# 005.net
KiCad netlist of a schematic drawn in EAGLE
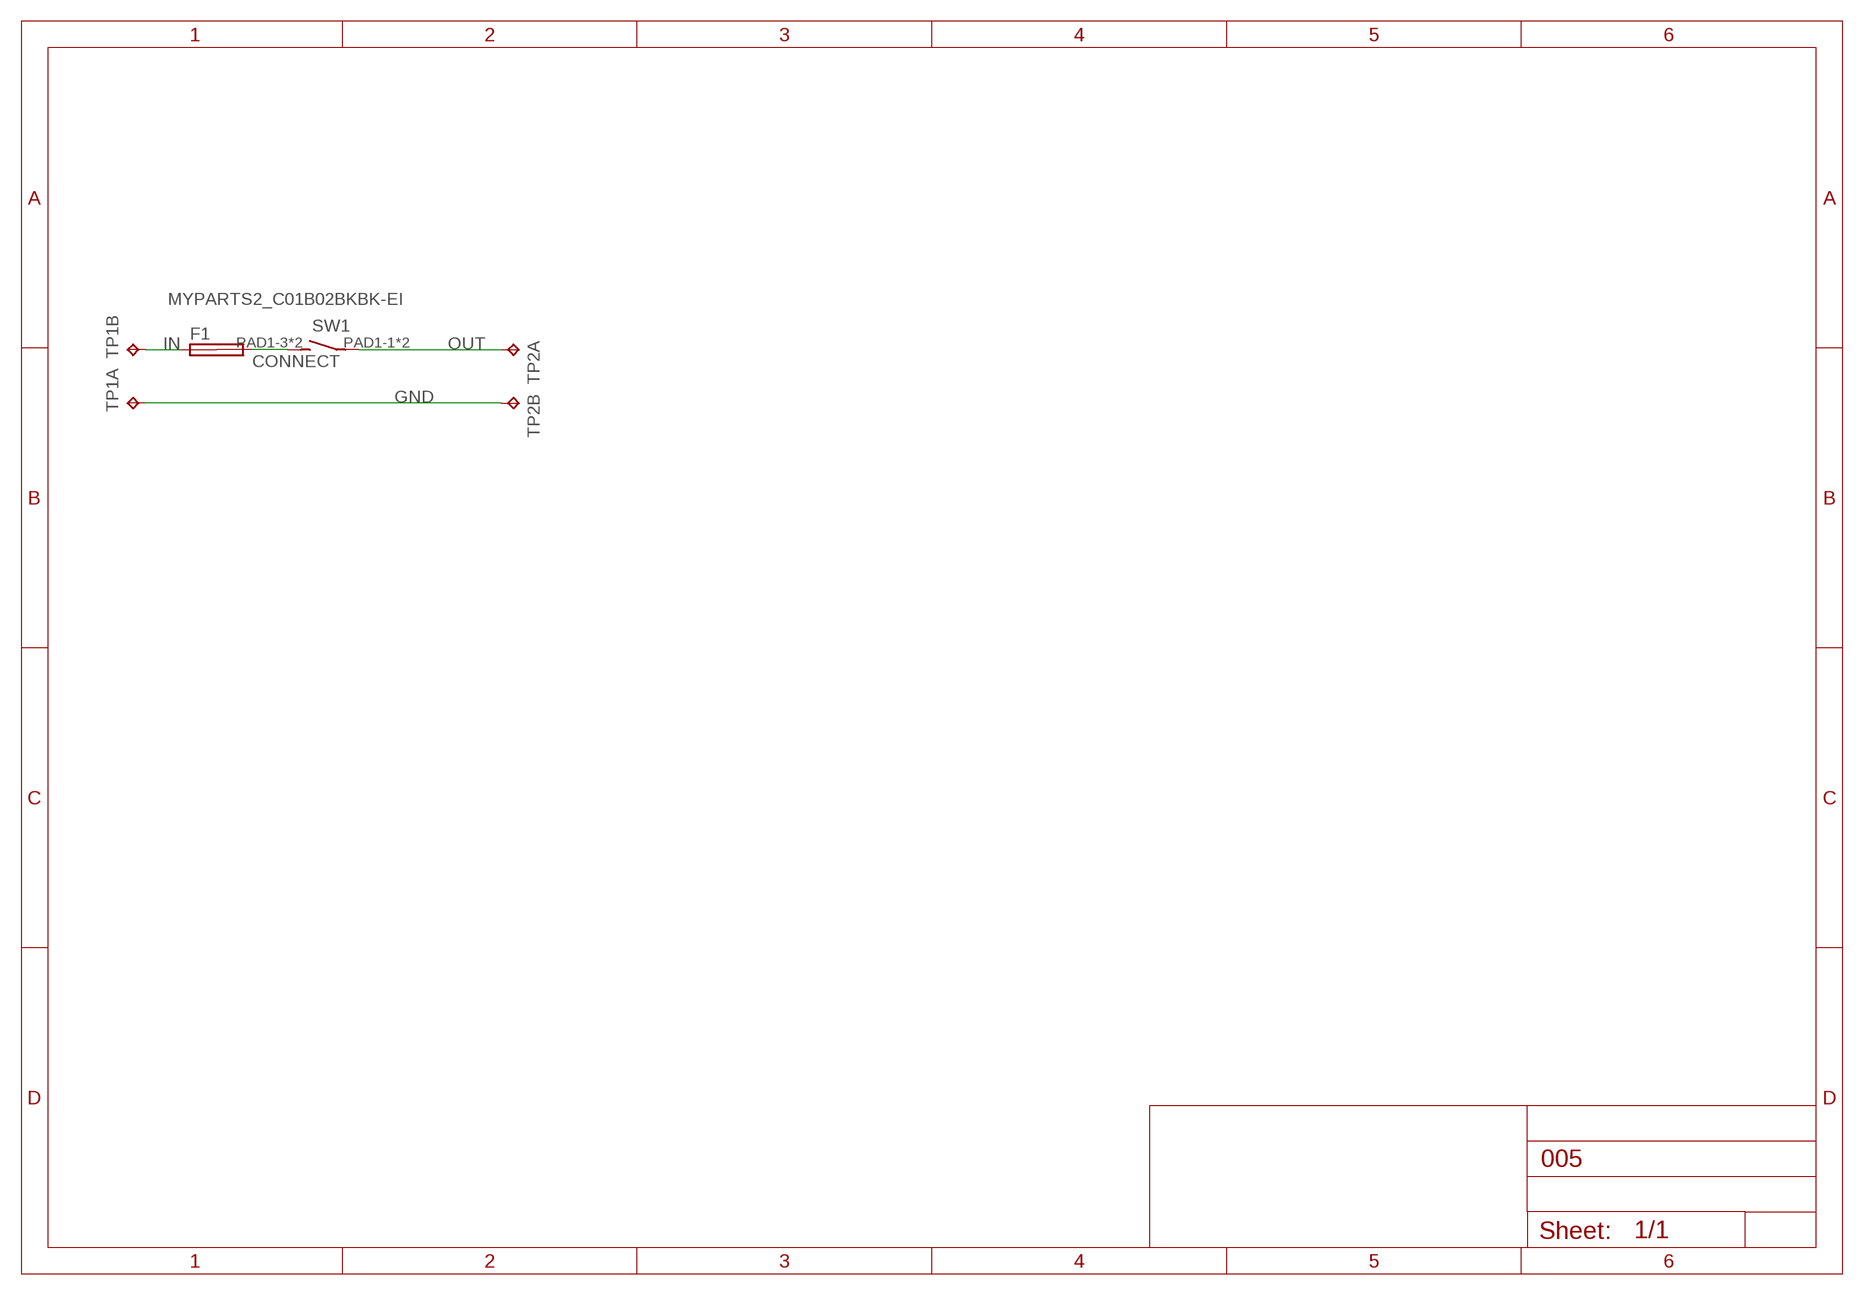
[diagram p0: schematic, sheet 1]

(export (version "E")
  (design (tool "Eeschema 10.0.6"))
  (components
    (comp (ref "F1")
      (value "SHK20L")
      (footprint "eagle-import:SHK20L")
      (libsource (lib "eagle-import") (part "SHK20L"))
    )
    (comp (ref "SW1")
      (value "MYPARTS2_C01B02BKBK-EI")
      (footprint "eagle-import:MYPARTS2_C01B02BKBK-EI")
      (libsource (lib "eagle-import") (part "MYPARTS2_C01B02BKBK-EI"))
    )
    (comp (ref "TP1")
      (value "TP2P2-38-20")
      (footprint "eagle-import:P2-38-20")
      (libsource (lib "eagle-import") (part "TP2P2-38-20"))
    )
    (comp (ref "TP2")
      (value "TP2P2-38-20")
      (footprint "eagle-import:P2-38-20")
      (libsource (lib "eagle-import") (part "TP2P2-38-20"))
    )
  )
  (nets
    (net (code "1") (name "/CONNECT") (class "Default")
      (node (ref "F1") (pin "2A") (pinfunction "2A_2A") (pintype "passive"))
      (node (ref "SW1") (pin "PAD1-3") (pinfunction "S_PAD1-3") (pintype "passive"))
      (node (ref "SW1") (pin "PAD1-4") (pinfunction "S_PAD1-4") (pintype "passive"))
    )
    (net (code "2") (name "/GND") (class "Default")
      (node (ref "TP1") (pin "TP-1") (pinfunction "TP_TP-1") (pintype "input"))
      (node (ref "TP2") (pin "TP-2") (pinfunction "TP_TP-2") (pintype "input"))
    )
    (net (code "3") (name "/IN") (class "Default")
      (node (ref "F1") (pin "1A") (pinfunction "1A_1A") (pintype "passive"))
      (node (ref "TP1") (pin "TP-2") (pinfunction "TP_TP-2") (pintype "input"))
    )
    (net (code "4") (name "/OUT") (class "Default")
      (node (ref "SW1") (pin "PAD1-1") (pinfunction "P_PAD1-1") (pintype "passive"))
      (node (ref "SW1") (pin "PAD1-2") (pinfunction "P_PAD1-2") (pintype "passive"))
      (node (ref "TP2") (pin "TP-1") (pinfunction "TP_TP-1") (pintype "input"))
    )
    (net (code "5") (name "unconnected-(F1-Pad1B)") (class "Default")
      (node (ref "F1") (pin "1B") (pinfunction "1B_1B") (pintype "passive"))
    )
    (net (code "6") (name "unconnected-(F1-Pad2B)") (class "Default")
      (node (ref "F1") (pin "2B") (pinfunction "2B_2B") (pintype "passive"))
    )
  )
)
